# receiver.net
KiCad netlist of a schematic drawn in EAGLE
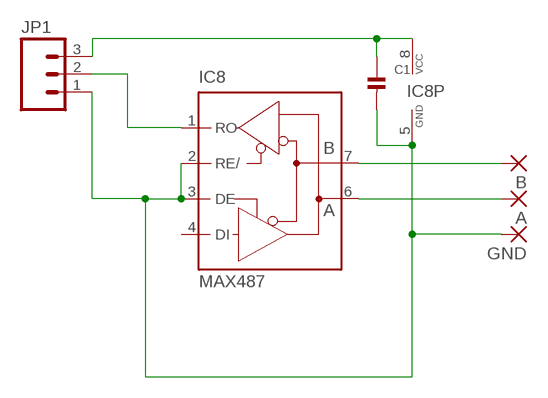
[diagram p0: schematic, sheet 1]

(export (version "E")
  (design (tool "Eeschema 10.0.6"))
  (components
    (comp (ref "A")
      (value "SMD5")
      (footprint "eagle-import:SMD2,54-5,08")
      (libsource (lib "eagle-import") (part "SMD5"))
    )
    (comp (ref "B")
      (value "SMD5")
      (footprint "eagle-import:SMD2,54-5,08")
      (libsource (lib "eagle-import") (part "SMD5"))
    )
    (comp (ref "C1")
      (value "CAP_CERAMIC0805")
      (footprint "eagle-import:0805")
      (libsource (lib "eagle-import") (part "CAP_CERAMIC0805"))
    )
    (comp (ref "GND")
      (value "SMD5")
      (footprint "eagle-import:SMD2,54-5,08")
      (libsource (lib "eagle-import") (part "SMD5"))
    )
    (comp (ref "IC8")
      (value "MAX487")
      (footprint "eagle-import:SO08")
      (fields (field (name "MF") "MAXIM") (field (name "MPN") "MAX481CSA"))
      (libsource (lib "eagle-import") (part "MAX481CSA"))
    )
    (comp (ref "JP1")
      (value "M03PTH")
      (footprint "eagle-import:1X03")
      (libsource (lib "eagle-import") (part "M03PTH"))
    )
  )
  (nets
    (net (code "1") (name "Net-(A-P)") (class "Default")
      (node (ref "A") (pin "1") (pinfunction "P_1") (pintype "passive"))
      (node (ref "IC8") (pin "6") (pinfunction "A_6") (pintype "passive"))
    )
    (net (code "2") (name "Net-(B-P)") (class "Default")
      (node (ref "B") (pin "1") (pinfunction "P_1") (pintype "passive"))
      (node (ref "IC8") (pin "7") (pinfunction "B_7") (pintype "passive"))
    )
    (net (code "3") (name "Net-(C1-P$1)") (class "Default")
      (node (ref "C1") (pin "1") (pinfunction "P$1_1") (pintype "passive"))
      (node (ref "IC8") (pin "8") (pinfunction "VCC_8") (pintype "power_in"))
      (node (ref "JP1") (pin "3") (pinfunction "3_3") (pintype "passive"))
    )
    (net (code "4") (name "Net-(C1-P$2)") (class "Default")
      (node (ref "C1") (pin "2") (pinfunction "P$2_2") (pintype "passive"))
      (node (ref "GND") (pin "1") (pinfunction "P_1") (pintype "passive"))
      (node (ref "IC8") (pin "2") (pinfunction "RE/_2") (pintype "input"))
      (node (ref "IC8") (pin "3") (pinfunction "DE_3") (pintype "input"))
      (node (ref "IC8") (pin "5") (pinfunction "GND_5") (pintype "power_in"))
      (node (ref "JP1") (pin "1") (pinfunction "1_1") (pintype "passive"))
    )
    (net (code "5") (name "Net-(IC8A-RO)") (class "Default")
      (node (ref "IC8") (pin "1") (pinfunction "RO_1") (pintype "output"))
      (node (ref "JP1") (pin "2") (pinfunction "2_2") (pintype "passive"))
    )
    (net (code "6") (name "unconnected-(IC8A-DI-Pad4)") (class "Default")
      (node (ref "IC8") (pin "4") (pinfunction "DI_4") (pintype "input"))
    )
  )
)
